# IMU.net
KiCad netlist of a schematic drawn in Altium Designer
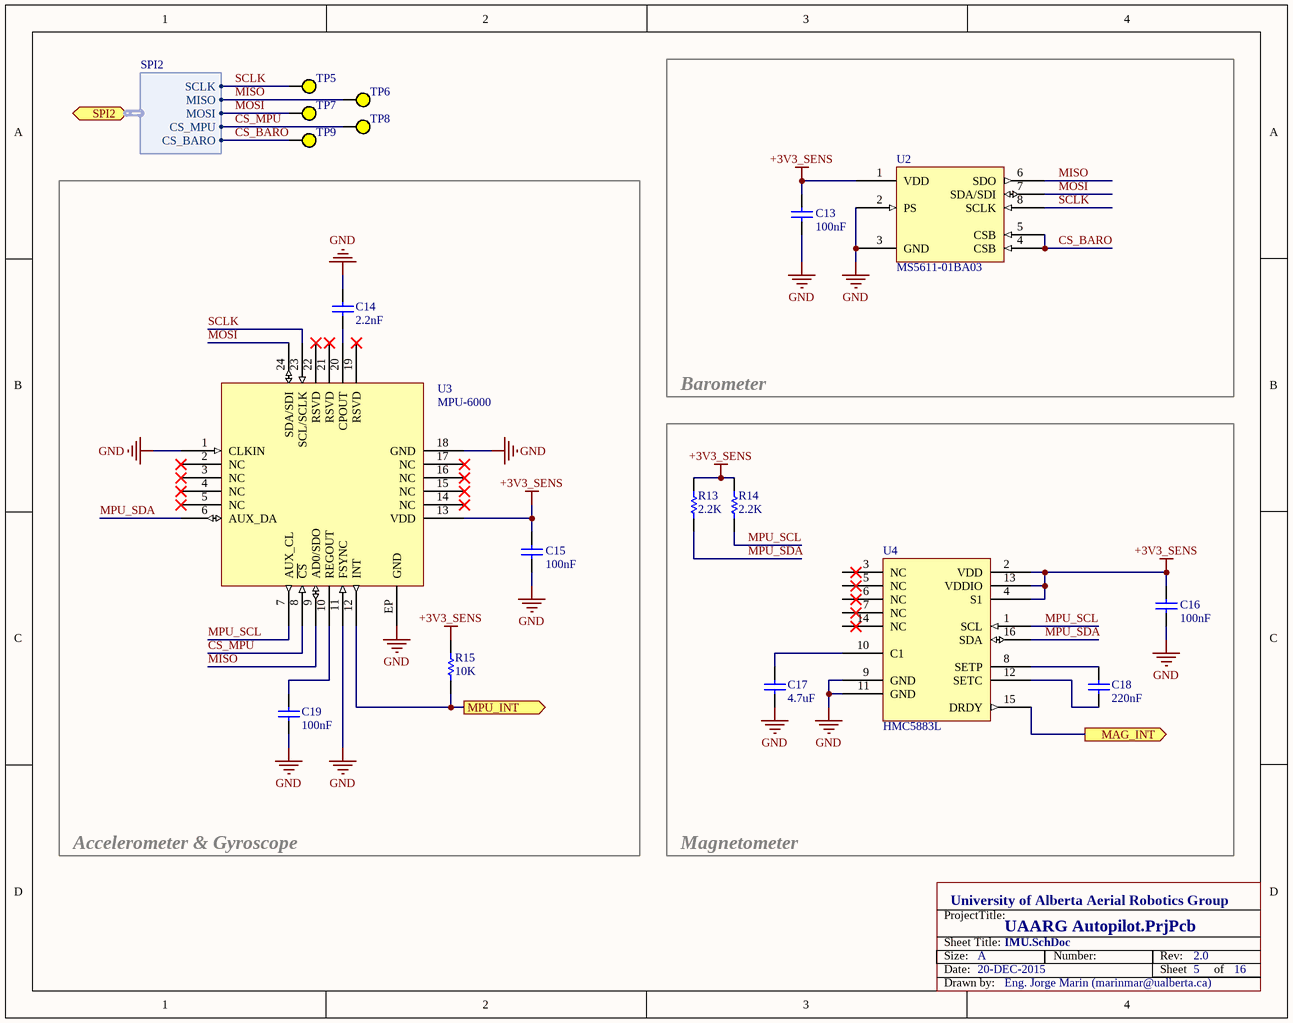
[diagram p0: IMU.SchDoc]

(export (version "E")
  (design (tool "Eeschema 10.0.6"))
  (components
    (comp (ref "C13")
      (value "100nF")
      (footprint "CAP_0402[1005M]")
      (description "Capacitor")
      (fields
        (field (name "MANUFACTURER") "Yageo")
        (field (name "MANUFACTURER PART NUMBER") "CC0402KRX7R6BB104")
      )
      (libsource (lib "UAARG Autopilot") (part "CAP"))
    )
    (comp (ref "C14")
      (value "2.2nF")
      (footprint "CAP_0402[1005M]")
      (description "Capacitor")
      (fields
        (field (name "MANUFACTURER") "Yageo")
        (field (name "MANUFACTURER PART NUMBER") "CC0402KRX7R9BB222")
      )
      (libsource (lib "UAARG Autopilot") (part "CAP"))
    )
    (comp (ref "C15")
      (value "100nF")
      (footprint "CAP_0402[1005M]")
      (description "Capacitor")
      (fields
        (field (name "MANUFACTURER") "Yageo")
        (field (name "MANUFACTURER PART NUMBER") "CC0402KRX7R6BB104")
      )
      (libsource (lib "UAARG Autopilot") (part "CAP"))
    )
    (comp (ref "C16")
      (value "100nF")
      (footprint "CAP_0402[1005M]")
      (description "Capacitor")
      (fields
        (field (name "MANUFACTURER") "Yageo")
        (field (name "MANUFACTURER PART NUMBER") "CC0402KRX7R6BB104")
      )
      (libsource (lib "UAARG Autopilot") (part "CAP"))
    )
    (comp (ref "C17")
      (value "4.7uF")
      (footprint "CAP_0402[1005M]")
      (description "Capacitor")
      (fields
        (field (name "MANUFACTURER") "Yageo")
        (field (name "MANUFACTURER PART NUMBER") "CC0402MRX5R6BB475")
      )
      (libsource (lib "UAARG Autopilot") (part "CAP"))
    )
    (comp (ref "C18")
      (value "220nF")
      (footprint "CAP_0402[1005M]")
      (description "Capacitor")
      (fields
        (field (name "MANUFACTURER") "Yageo")
        (field (name "MANUFACTURER PART NUMBER") "CC0402KRX5R5BB224")
      )
      (libsource (lib "UAARG Autopilot") (part "CAP"))
    )
    (comp (ref "C19")
      (value "100nF")
      (footprint "CAP_0402[1005M]")
      (description "Capacitor")
      (fields
        (field (name "MANUFACTURER") "Yageo")
        (field (name "MANUFACTURER PART NUMBER") "CC0402KRX7R6BB104")
      )
      (libsource (lib "UAARG Autopilot") (part "CAP"))
    )
    (comp (ref "R13")
      (value "2.2K")
      (footprint "RES_0402[1005M]")
      (description "Resistor")
      (fields
        (field (name "MANUFACTURER PART NUMBER") "RC0402FR-072K2L")
        (field (name "MANUFACTURER") "Yageo")
      )
      (libsource (lib "UAARG Autopilot") (part "RES"))
    )
    (comp (ref "R14")
      (value "2.2K")
      (footprint "RES_0402[1005M]")
      (description "Resistor")
      (fields
        (field (name "MANUFACTURER PART NUMBER") "RC0402FR-072K2L")
        (field (name "MANUFACTURER") "Yageo")
      )
      (libsource (lib "UAARG Autopilot") (part "RES"))
    )
    (comp (ref "R15")
      (value "10K")
      (footprint "RES_0402[1005M]")
      (description "Resistor")
      (fields
        (field (name "MANUFACTURER") "Yageo")
        (field (name "MANUFACTURER PART NUMBER") "RC0402FR-0710KL")
      )
      (libsource (lib "UAARG Autopilot") (part "RES"))
    )
    (comp (ref "TP5")
      (value "Test Point SIG")
      (footprint "TP_SMD_1_SILK")
      (description "Test Point Signal")
      (libsource (lib "UAARG Autopilot") (part "Test Point SIG"))
    )
    (comp (ref "TP6")
      (value "Test Point SIG")
      (footprint "TP_SMD_1_SILK")
      (description "Test Point Signal")
      (libsource (lib "UAARG Autopilot") (part "Test Point SIG"))
    )
    (comp (ref "TP7")
      (value "Test Point SIG")
      (footprint "TP_SMD_1_SILK")
      (description "Test Point Signal")
      (libsource (lib "UAARG Autopilot") (part "Test Point SIG"))
    )
    (comp (ref "TP8")
      (value "Test Point SIG")
      (footprint "TP_SMD_1_SILK")
      (description "Test Point Signal")
      (libsource (lib "UAARG Autopilot") (part "Test Point SIG"))
    )
    (comp (ref "TP9")
      (value "Test Point SIG")
      (footprint "TP_SMD_1_SILK")
      (description "Test Point Signal")
      (libsource (lib "UAARG Autopilot") (part "Test Point SIG"))
    )
    (comp (ref "U2")
      (value "MS5611-01BA03")
      (footprint "MS5611-01BA03")
      (description "MS5611-01BA03 Barometer, Altimeter")
      (fields
        (field (name "MANUFACTURER") "Measurement Specialties, Inc.")
        (field (name "MANUFACTURER PART NUMBER") "MS5611-01BA03")
      )
      (libsource (lib "UAARG Autopilot") (part "MS5611-01BA03"))
    )
    (comp (ref "U3")
      (value "MPU-6000")
      (footprint "QFN24")
      (description "Invense MPU-6000 6 Axis Motion Sensor")
      (fields (field (name "MANUFACTURER") "InvenSense") (field (name "MANUFACTURER PART NUMBER") "MPU-6000"))
      (libsource (lib "UAARG Autopilot") (part "MPU-6000"))
    )
    (comp (ref "U4")
      (value "HMC5883L")
      (footprint "QFN16")
      (description "HMC5883L 3-axis Magnetometer")
      (fields
        (field (name "MANUFACTURER") "Honeywell Microelectronics & Precision Sensors")
        (field (name "MANUFACTURER PART NUMBER") "HMC5883L-TR")
      )
      (libsource (lib "UAARG Autopilot") (part "HMC5883L"))
    )
  )
  (nets
    (net (code "2") (name "+3V3_SENS") (class "Default")
      (node (ref "C13") (pin "1") (pinfunction "1_1") (pintype "passive"))
      (node (ref "C15") (pin "1") (pinfunction "1_1") (pintype "passive"))
      (node (ref "C16") (pin "1") (pinfunction "1_1") (pintype "passive"))
      (node (ref "R13") (pin "2") (pinfunction "2_2") (pintype "passive"))
      (node (ref "R14") (pin "2") (pinfunction "2_2") (pintype "passive"))
      (node (ref "R15") (pin "2") (pinfunction "2_2") (pintype "passive"))
      (node (ref "U2") (pin "1") (pinfunction "VDD_1") (pintype "power_in"))
      (node (ref "U3") (pin "13") (pinfunction "VDD_13") (pintype "power_in"))
      (node (ref "U4") (pin "13") (pinfunction "VDDIO_13") (pintype "power_in"))
      (node (ref "U4") (pin "2") (pinfunction "VDD_2") (pintype "power_in"))
      (node (ref "U4") (pin "4") (pinfunction "S1_4") (pintype "passive"))
    )
    (net (code "3") (name "/CS_BARO") (class "Default")
      (node (ref "TP9") (pin "1") (pinfunction "1_1") (pintype "passive"))
      (node (ref "U2") (pin "4") (pinfunction "CSB_4") (pintype "input"))
      (node (ref "U2") (pin "5") (pinfunction "CSB_5") (pintype "input"))
    )
    (net (code "4") (name "/CS_MPU") (class "Default")
      (node (ref "TP8") (pin "1") (pinfunction "1_1") (pintype "passive"))
      (node (ref "U3") (pin "8") (pinfunction "~{CS}_8") (pintype "input"))
    )
    (net (code "5") (name "/MAG_INT") (class "Default")
      (node (ref "U4") (pin "15") (pinfunction "DRDY_15") (pintype "output"))
    )
    (net (code "6") (name "/MISO") (class "Default")
      (node (ref "TP6") (pin "1") (pinfunction "1_1") (pintype "passive"))
      (node (ref "U2") (pin "6") (pinfunction "SDO_6") (pintype "output"))
      (node (ref "U3") (pin "9") (pinfunction "AD0/SDO_9") (pintype "bidirectional"))
    )
    (net (code "7") (name "/MOSI") (class "Default")
      (node (ref "TP7") (pin "1") (pinfunction "1_1") (pintype "passive"))
      (node (ref "U2") (pin "7") (pinfunction "SDA/SDI_7") (pintype "bidirectional"))
      (node (ref "U3") (pin "24") (pinfunction "SDA/SDI_24") (pintype "bidirectional"))
    )
    (net (code "8") (name "/MPU_INT") (class "Default")
      (node (ref "R15") (pin "1") (pinfunction "1_1") (pintype "passive"))
      (node (ref "U3") (pin "12") (pinfunction "INT_12") (pintype "output"))
    )
    (net (code "9") (name "/MPU_SCL") (class "Default")
      (node (ref "R14") (pin "1") (pinfunction "1_1") (pintype "passive"))
      (node (ref "U3") (pin "7") (pinfunction "AUX_CL_7") (pintype "output"))
      (node (ref "U4") (pin "1") (pinfunction "SCL_1") (pintype "input"))
    )
    (net (code "10") (name "/MPU_SDA") (class "Default")
      (node (ref "R13") (pin "1") (pinfunction "1_1") (pintype "passive"))
      (node (ref "U3") (pin "6") (pinfunction "AUX_DA_6") (pintype "bidirectional"))
      (node (ref "U4") (pin "16") (pinfunction "SDA_16") (pintype "bidirectional"))
    )
    (net (code "11") (name "/SCLK") (class "Default")
      (node (ref "TP5") (pin "1") (pinfunction "1_1") (pintype "passive"))
      (node (ref "U2") (pin "8") (pinfunction "SCLK_8") (pintype "input"))
      (node (ref "U3") (pin "23") (pinfunction "SCL/SCLK_23") (pintype "input"))
    )
    (net (code "13") (name "GND") (class "Default")
      (node (ref "C13") (pin "2") (pinfunction "2_2") (pintype "passive"))
      (node (ref "C14") (pin "2") (pinfunction "2_2") (pintype "passive"))
      (node (ref "C15") (pin "2") (pinfunction "2_2") (pintype "passive"))
      (node (ref "C16") (pin "2") (pinfunction "2_2") (pintype "passive"))
      (node (ref "C17") (pin "2") (pinfunction "2_2") (pintype "passive"))
      (node (ref "C19") (pin "1") (pinfunction "1_1") (pintype "passive"))
      (node (ref "U2") (pin "2") (pinfunction "PS_2") (pintype "input"))
      (node (ref "U2") (pin "3") (pinfunction "GND_3") (pintype "power_in"))
      (node (ref "U3") (pin "1") (pinfunction "CLKIN_1") (pintype "input"))
      (node (ref "U3") (pin "11") (pinfunction "FSYNC_11") (pintype "input"))
      (node (ref "U3") (pin "18") (pinfunction "GND_18") (pintype "power_in"))
      (node (ref "U3") (pin "EP") (pinfunction "GND_EP") (pintype "power_in"))
      (node (ref "U4") (pin "11") (pinfunction "GND_11") (pintype "power_in"))
      (node (ref "U4") (pin "9") (pinfunction "GND_9") (pintype "power_in"))
    )
    (net (code "14") (name "Net-(U3-CPOUT)") (class "Default")
      (node (ref "C14") (pin "1") (pinfunction "1_1") (pintype "passive"))
      (node (ref "U3") (pin "20") (pinfunction "CPOUT_20") (pintype "power_in"))
    )
    (net (code "15") (name "Net-(U3-REGOUT)") (class "Default")
      (node (ref "C19") (pin "2") (pinfunction "2_2") (pintype "passive"))
      (node (ref "U3") (pin "10") (pinfunction "REGOUT_10") (pintype "power_in"))
    )
    (net (code "16") (name "Net-(U4-C1)") (class "Default")
      (node (ref "C17") (pin "1") (pinfunction "1_1") (pintype "passive"))
      (node (ref "U4") (pin "10") (pinfunction "C1_10") (pintype "passive"))
    )
    (net (code "17") (name "Net-(U4-SETC)") (class "Default")
      (node (ref "C18") (pin "2") (pinfunction "2_2") (pintype "passive"))
      (node (ref "U4") (pin "12") (pinfunction "SETC_12") (pintype "passive"))
    )
    (net (code "18") (name "Net-(U4-SETP)") (class "Default")
      (node (ref "C18") (pin "1") (pinfunction "1_1") (pintype "passive"))
      (node (ref "U4") (pin "8") (pinfunction "SETP_8") (pintype "passive"))
    )
    (net (code "19") (name "unconnected-(U3-NC-Pad2)") (class "Default")
      (node (ref "U3") (pin "2") (pinfunction "NC_2") (pintype "passive+no_connect"))
    )
    (net (code "20") (name "unconnected-(U3-NC-Pad3)") (class "Default")
      (node (ref "U3") (pin "3") (pinfunction "NC_3") (pintype "passive+no_connect"))
    )
    (net (code "21") (name "unconnected-(U3-NC-Pad4)") (class "Default")
      (node (ref "U3") (pin "4") (pinfunction "NC_4") (pintype "passive+no_connect"))
    )
    (net (code "22") (name "unconnected-(U3-NC-Pad5)") (class "Default")
      (node (ref "U3") (pin "5") (pinfunction "NC_5") (pintype "passive+no_connect"))
    )
    (net (code "23") (name "unconnected-(U3-NC-Pad14)") (class "Default")
      (node (ref "U3") (pin "14") (pinfunction "NC_14") (pintype "passive+no_connect"))
    )
    (net (code "24") (name "unconnected-(U3-NC-Pad15)") (class "Default")
      (node (ref "U3") (pin "15") (pinfunction "NC_15") (pintype "passive+no_connect"))
    )
    (net (code "25") (name "unconnected-(U3-NC-Pad16)") (class "Default")
      (node (ref "U3") (pin "16") (pinfunction "NC_16") (pintype "passive+no_connect"))
    )
    (net (code "26") (name "unconnected-(U3-NC-Pad17)") (class "Default")
      (node (ref "U3") (pin "17") (pinfunction "NC_17") (pintype "passive+no_connect"))
    )
    (net (code "27") (name "unconnected-(U3-RSVD-Pad19)") (class "Default")
      (node (ref "U3") (pin "19") (pinfunction "RSVD_19") (pintype "passive+no_connect"))
    )
    (net (code "28") (name "unconnected-(U3-RSVD-Pad21)") (class "Default")
      (node (ref "U3") (pin "21") (pinfunction "RSVD_21") (pintype "passive+no_connect"))
    )
    (net (code "29") (name "unconnected-(U3-RSVD-Pad22)") (class "Default")
      (node (ref "U3") (pin "22") (pinfunction "RSVD_22") (pintype "passive+no_connect"))
    )
    (net (code "30") (name "unconnected-(U4-NC-Pad3)") (class "Default")
      (node (ref "U4") (pin "3") (pinfunction "NC_3") (pintype "passive"))
    )
    (net (code "31") (name "unconnected-(U4-NC-Pad5)") (class "Default")
      (node (ref "U4") (pin "5") (pinfunction "NC_5") (pintype "passive"))
    )
    (net (code "32") (name "unconnected-(U4-NC-Pad6)") (class "Default")
      (node (ref "U4") (pin "6") (pinfunction "NC_6") (pintype "passive"))
    )
    (net (code "33") (name "unconnected-(U4-NC-Pad7)") (class "Default")
      (node (ref "U4") (pin "7") (pinfunction "NC_7") (pintype "passive"))
    )
    (net (code "34") (name "unconnected-(U4-NC-Pad14)") (class "Default")
      (node (ref "U4") (pin "14") (pinfunction "NC_14") (pintype "passive"))
    )
  )
)
